# Quad_FC_V10_7-final.net
KiCad netlist of a schematic drawn in Altium Designer
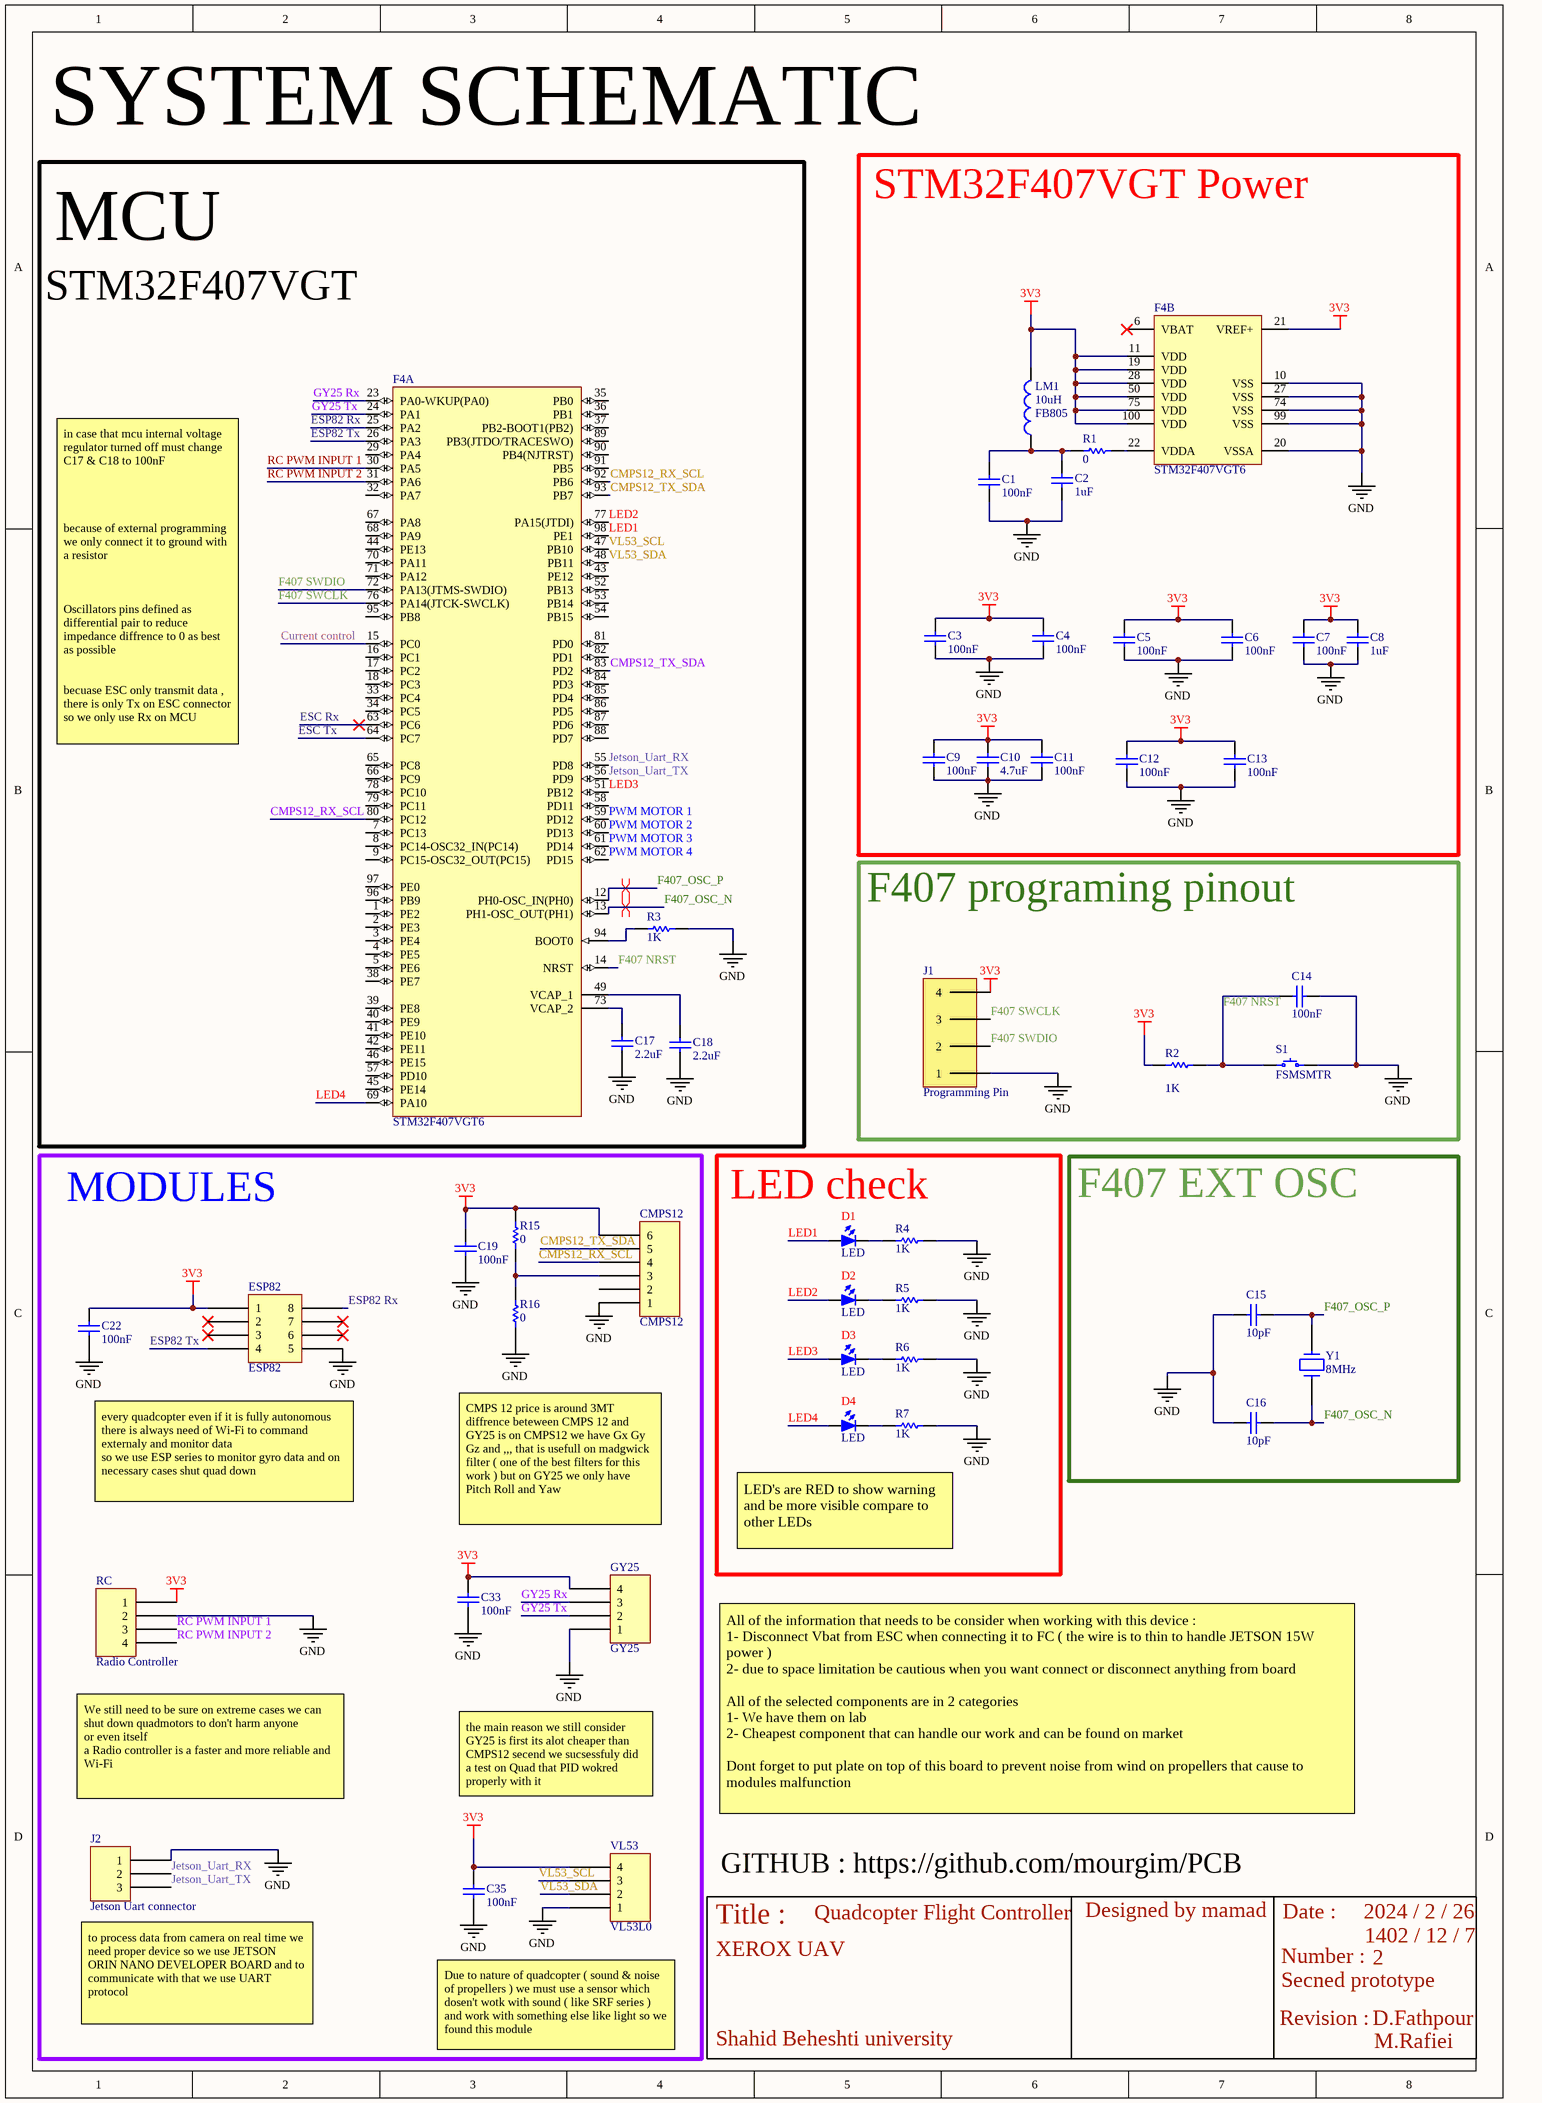
[diagram p0: Quad FC V10.7-final.SchDoc]

(export (version "E")
  (design (tool "Eeschema 10.0.6"))
  (components
    (comp (ref "C1")
      (value "100nF")
      (footprint "CAP0603")
      (description "F407VET6 Power CAP")
      (fields (field (name "DESIGNER") "Abbas Basereh"))
      (libsource (lib "2017AbbasBasereh9365731239 -ver1") (part "CAP SMD PACKAGE"))
    )
    (comp (ref "C2")
      (value "1uF")
      (footprint "CAP0603")
      (description "F407VET6 Power CAP")
      (fields (field (name "DESIGNER") "Abbas Basereh"))
      (libsource (lib "2017AbbasBasereh9365731239 -ver1") (part "CAP SMD PACKAGE"))
    )
    (comp (ref "C3")
      (value "100nF")
      (footprint "CAP0603")
      (description "F407VET6 Power CAP")
      (fields (field (name "DESIGNER") "Abbas Basereh"))
      (libsource (lib "2017AbbasBasereh9365731239 -ver1") (part "CAP SMD PACKAGE"))
    )
    (comp (ref "C4")
      (value "100nF")
      (footprint "CAP0603")
      (description "F407VET6 Power CAP")
      (fields (field (name "DESIGNER") "Abbas Basereh"))
      (libsource (lib "2017AbbasBasereh9365731239 -ver1") (part "CAP SMD PACKAGE"))
    )
    (comp (ref "C5")
      (value "100nF")
      (footprint "CAP0603")
      (description "F407VET6 Power CAP")
      (fields (field (name "DESIGNER") "Abbas Basereh"))
      (libsource (lib "2017AbbasBasereh9365731239 -ver1") (part "CAP SMD PACKAGE"))
    )
    (comp (ref "C6")
      (value "100nF")
      (footprint "CAP0603")
      (description "F407VET6 Power CAP")
      (fields (field (name "DESIGNER") "Abbas Basereh"))
      (libsource (lib "2017AbbasBasereh9365731239 -ver1") (part "CAP SMD PACKAGE"))
    )
    (comp (ref "C7")
      (value "100nF")
      (footprint "CAP0603")
      (description "F407VET6 Power CAP")
      (fields (field (name "DESIGNER") "Abbas Basereh"))
      (libsource (lib "2017AbbasBasereh9365731239 -ver1") (part "CAP SMD PACKAGE"))
    )
    (comp (ref "C8")
      (value "1uF")
      (footprint "CAP0603")
      (description "F407VET6 Power CAP")
      (fields (field (name "DESIGNER") "Abbas Basereh"))
      (libsource (lib "2017AbbasBasereh9365731239 -ver1") (part "CAP SMD PACKAGE"))
    )
    (comp (ref "C9")
      (value "100nF")
      (footprint "CAP0603")
      (description "F407VET6 Power CAP")
      (fields (field (name "DESIGNER") "Abbas Basereh"))
      (libsource (lib "2017AbbasBasereh9365731239 -ver1") (part "CAP SMD PACKAGE"))
    )
    (comp (ref "C10")
      (value "4.7uF")
      (footprint "CAP0603")
      (description "F407VET6 Power CAP")
      (fields (field (name "DESIGNER") "Abbas Basereh"))
      (libsource (lib "2017AbbasBasereh9365731239 -ver1") (part "CAP SMD PACKAGE"))
    )
    (comp (ref "C11")
      (value "100nF")
      (footprint "CAP0603")
      (description "F407VET6 Power CAP")
      (fields (field (name "DESIGNER") "Abbas Basereh"))
      (libsource (lib "2017AbbasBasereh9365731239 -ver1") (part "CAP SMD PACKAGE"))
    )
    (comp (ref "C12")
      (value "100nF")
      (footprint "CAP0603")
      (description "F407VET6 Power CAP")
      (fields (field (name "DESIGNER") "Abbas Basereh"))
      (libsource (lib "2017AbbasBasereh9365731239 -ver1") (part "CAP SMD PACKAGE"))
    )
    (comp (ref "C13")
      (value "100nF")
      (footprint "CAP0603")
      (description "F407VET6 Power CAP")
      (fields (field (name "DESIGNER") "Abbas Basereh"))
      (libsource (lib "2017AbbasBasereh9365731239 -ver1") (part "CAP SMD PACKAGE"))
    )
    (comp (ref "C14")
      (value "100nF")
      (footprint "CAP0603")
      (description "F407VET6 Power CAP")
      (fields (field (name "DESIGNER") "Abbas Basereh"))
      (libsource (lib "2017AbbasBasereh9365731239 -ver1") (part "CAP SMD PACKAGE"))
    )
    (comp (ref "C15")
      (value "10pF")
      (footprint "CAP0603")
      (description "F407VET6 Power CAP")
      (fields (field (name "DESIGNER") "Abbas Basereh"))
      (libsource (lib "2017AbbasBasereh9365731239 -ver1") (part "CAP SMD PACKAGE"))
    )
    (comp (ref "C16")
      (value "10pF")
      (footprint "CAP0603")
      (description "F407VET6 Power CAP")
      (fields (field (name "DESIGNER") "Abbas Basereh"))
      (libsource (lib "2017AbbasBasereh9365731239 -ver1") (part "CAP SMD PACKAGE"))
    )
    (comp (ref "C17")
      (value "2.2uF")
      (footprint "CAP0603")
      (description "F407VET6 Power CAP")
      (fields (field (name "DESIGNER") "Abbas Basereh"))
      (libsource (lib "2017AbbasBasereh9365731239 -ver1") (part "CAP SMD PACKAGE"))
    )
    (comp (ref "C18")
      (value "2.2uF")
      (footprint "CAP0603")
      (description "F407VET6 Power CAP")
      (fields (field (name "DESIGNER") "Abbas Basereh"))
      (libsource (lib "2017AbbasBasereh9365731239 -ver1") (part "CAP SMD PACKAGE"))
    )
    (comp (ref "C19")
      (value "100nF")
      (footprint "CAP0603")
      (description "F407VET6 Power CAP")
      (fields (field (name "DESIGNER") "Abbas Basereh"))
      (libsource (lib "2017AbbasBasereh9365731239 -ver1") (part "CAP SMD PACKAGE"))
    )
    (comp (ref "C22")
      (value "100nF")
      (footprint "CAP0603")
      (description "F407VET6 Power CAP")
      (fields (field (name "DESIGNER") "Abbas Basereh"))
      (libsource (lib "2017AbbasBasereh9365731239 -ver1") (part "CAP SMD PACKAGE"))
    )
    (comp (ref "C33")
      (value "100nF")
      (footprint "CAP0603")
      (description "F407VET6 Power CAP")
      (fields (field (name "DESIGNER") "Abbas Basereh"))
      (libsource (lib "2017AbbasBasereh9365731239 -ver1") (part "CAP SMD PACKAGE"))
    )
    (comp (ref "C35")
      (value "100nF")
      (footprint "CAP0603")
      (description "F407VET6 Power CAP")
      (fields (field (name "DESIGNER") "Abbas Basereh"))
      (libsource (lib "2017AbbasBasereh9365731239 -ver1") (part "CAP SMD PACKAGE"))
    )
    (comp (ref "CMPS12")
      (value "CMPS12")
      (footprint "SAMTEC SSW-106-03-T-S")
      (description "CONN RCPT 6POS 0.1 TIN PCB")
      (fields (field (name "PART NUMBER") "SSW-106-03-T-S") (field (name "MANUFACTURER") "Samtec Inc."))
      (libsource (lib "Celestial Altium Library - altium_library (1)") (part "6 Pin"))
    )
    (comp (ref "D1")
      (value "LED")
      (footprint "0603 - LED")
      (description "Led")
      (fields (field (name "PUBLISHER") "Altium Limited"))
      (libsource (lib "Sajad_Altium_Library") (part "LED"))
    )
    (comp (ref "D2")
      (value "LED")
      (footprint "0603 - LED")
      (description "Led")
      (fields (field (name "PUBLISHER") "Altium Limited"))
      (libsource (lib "Sajad_Altium_Library") (part "LED"))
    )
    (comp (ref "D3")
      (value "LED")
      (footprint "0603 - LED")
      (description "Led")
      (fields (field (name "PUBLISHER") "Altium Limited"))
      (libsource (lib "Sajad_Altium_Library") (part "LED"))
    )
    (comp (ref "D4")
      (value "LED")
      (footprint "0603 - LED")
      (description "Led")
      (fields (field (name "PUBLISHER") "Altium Limited"))
      (libsource (lib "Sajad_Altium_Library") (part "LED"))
    )
    (comp (ref "ESP82")
      (value "ESP82")
      (footprint "HARWIN M20-7830445")
      (description "CONN RCPT 8POS 0.1 GOLD PCB")
      (fields (field (name "PART NUMBER") "M20-7830442") (field (name "MANUFACTURER") "Harwin Inc."))
      (libsource (lib "Celestial Altium Library - altium_library (1)") (part "2X4 PIN DU"))
    )
    (comp (ref "F4")
      (value "STM32F407VGT6")
      (footprint "STM-LQFP100_N")
      (fields (field (name "MANUFACTURER") "STMicroelectronics"))
      (libsource (lib "STMicroelectronics STM32 F4") (part "STM32F407VGT6"))
    )
    (comp (ref "GY25")
      (value "GY25")
      (footprint "SAMTEC SSW-104-03-T-S")
      (description "CONN RCPT 4POS 0.1 TIN PCB")
      (fields (field (name "PART NUMBER") "SSW-104-03-T-S") (field (name "MANUFACTURER") "Samtec Inc."))
      (libsource (lib "Celestial Altium Library - altium_library (1)") (part "4 Pin"))
    )
    (comp (ref "J1")
      (value "Programming Pin")
      (footprint "HEADER 4X1")
      (libsource (lib "AltiumLib1") (part "Header4X1"))
    )
    (comp (ref "J2")
      (value "Jetson Uart connector")
      (footprint "JST XH B3B-XH-A")
      (description "CONN HEADER VERT 3POS 2.5MM")
      (fields
        (field (name "PART NUMBER") "B3B-XH-A(LF)(SN)")
        (field (name "MANUFACTURER") "JST Sales America Inc.")
      )
      (libsource (lib "Celestial Altium Library - altium_library (1)") (part "3 Pin"))
    )
    (comp (ref "LM1")
      (value "10uH")
      (footprint "0805L")
      (description "Inductor")
      (fields (field (name "ALTIUM_VALUE") "FB805") (field (name "PUBLISHER") "Altium Limited"))
      (libsource (lib "2017AbbasBasereh9365731239 -ver1") (part "L SMA 0.25W"))
    )
    (comp (ref "R1")
      (value "0")
      (footprint "RES0603")
      (description "TOTAL SMD RESISTOR PACK")
      (fields (field (name "DESIGNER") "Abbas Basereh"))
      (libsource (lib "2017AbbasBasereh9365731239 -ver1") (part "RES SMD PACKAGE"))
    )
    (comp (ref "R2")
      (value "1K")
      (footprint "RES0603")
      (description "TOTAL SMD RESISTOR PACK")
      (fields (field (name "DESIGNER") "Abbas Basereh"))
      (libsource (lib "2017AbbasBasereh9365731239 -ver1") (part "RES SMD PACKAGE"))
    )
    (comp (ref "R3")
      (value "1K")
      (footprint "RES0603")
      (description "TOTAL SMD RESISTOR PACK")
      (fields (field (name "DESIGNER") "Abbas Basereh"))
      (libsource (lib "2017AbbasBasereh9365731239 -ver1") (part "RES SMD PACKAGE"))
    )
    (comp (ref "R4")
      (value "1K")
      (footprint "RES0603")
      (description "TOTAL SMD RESISTOR PACK")
      (fields (field (name "DESIGNER") "Abbas Basereh"))
      (libsource (lib "2017AbbasBasereh9365731239 -ver1") (part "RES SMD PACKAGE"))
    )
    (comp (ref "R5")
      (value "1K")
      (footprint "RES0603")
      (description "TOTAL SMD RESISTOR PACK")
      (fields (field (name "DESIGNER") "Abbas Basereh"))
      (libsource (lib "2017AbbasBasereh9365731239 -ver1") (part "RES SMD PACKAGE"))
    )
    (comp (ref "R6")
      (value "1K")
      (footprint "RES0603")
      (description "TOTAL SMD RESISTOR PACK")
      (fields (field (name "DESIGNER") "Abbas Basereh"))
      (libsource (lib "2017AbbasBasereh9365731239 -ver1") (part "RES SMD PACKAGE"))
    )
    (comp (ref "R7")
      (value "1K")
      (footprint "RES0603")
      (description "TOTAL SMD RESISTOR PACK")
      (fields (field (name "DESIGNER") "Abbas Basereh"))
      (libsource (lib "2017AbbasBasereh9365731239 -ver1") (part "RES SMD PACKAGE"))
    )
    (comp (ref "R15")
      (value "0")
      (footprint "RES0603")
      (description "TOTAL SMD RESISTOR PACK")
      (fields (field (name "DESIGNER") "Abbas Basereh"))
      (libsource (lib "2017AbbasBasereh9365731239 -ver1") (part "RES SMD PACKAGE"))
    )
    (comp (ref "R16")
      (value "0")
      (footprint "RES0603")
      (description "TOTAL SMD RESISTOR PACK")
      (fields (field (name "DESIGNER") "Abbas Basereh"))
      (libsource (lib "2017AbbasBasereh9365731239 -ver1") (part "RES SMD PACKAGE"))
    )
    (comp (ref "RC")
      (value "Radio Controller")
      (footprint "JST SM04B-GHS-TB")
      (description "CONN HEADER SMD R/A 4POS 1.25MM")
      (fields
        (field (name "PART NUMBER") "SM04B-GHS-TB(LF)(SN)-")
        (field (name "MANUFACTURER") "JST Sales America Inc.")
      )
      (libsource (lib "") (part "4 Pin_1"))
    )
    (comp (ref "S1")
      (value "FSMSMTR")
      (footprint "TE FSMSMTR")
      (description "SWITCH TACTILE SPST-NO 0.05A 24V")
      (fields (field (name "MANUFACTURER") "TE Connectivity ALCOSWITCH Switches"))
      (libsource (lib "Celestial Altium Library - altium_library (1)") (part "SPST-NO 2 PIN"))
    )
    (comp (ref "VL53")
      (value "VL53L0")
      (footprint "JST SM04B-GHS-TB")
      (description "CONN HEADER SMD R/A 4POS 1.25MM")
      (fields
        (field (name "PART NUMBER") "SM04B-GHS-TB(LF)(SN)-")
        (field (name "MANUFACTURER") "JST Sales America Inc.")
      )
      (libsource (lib "Celestial Altium Library - altium_library (1)") (part "4 Pin"))
    )
    (comp (ref "Y1")
      (value "8MHz")
      (footprint "My_Crystal - SMD")
      (description "Crystal")
      (libsource (lib "AMINLIB") (part "CRYSTAL_SMD"))
    )
  )
  (nets
    (net (code "1") (name "/CMPS12_RX_SCL") (class "Default")
      (node (ref "CMPS12") (pin "4") (pinfunction "4_4") (pintype "passive"))
      (node (ref "F4") (pin "80") (pinfunction "PC12_80") (pintype "bidirectional"))
      (node (ref "F4") (pin "92") (pinfunction "PB6_92") (pintype "bidirectional"))
    )
    (net (code "2") (name "/CMPS12_TX_SDA") (class "Default")
      (node (ref "CMPS12") (pin "5") (pinfunction "5_5") (pintype "passive"))
      (node (ref "F4") (pin "83") (pinfunction "PD2_83") (pintype "bidirectional"))
      (node (ref "F4") (pin "93") (pinfunction "PB7_93") (pintype "bidirectional"))
    )
    (net (code "3") (name "/Current control") (class "Default")
      (node (ref "F4") (pin "15") (pinfunction "PC0_15") (pintype "bidirectional"))
    )
    (net (code "4") (name "/ESC Rx") (class "Default")
      (node (ref "F4") (pin "63") (pinfunction "PC6_63") (pintype "bidirectional"))
    )
    (net (code "5") (name "/ESC Tx") (class "Default")
      (node (ref "F4") (pin "64") (pinfunction "PC7_64") (pintype "bidirectional"))
    )
    (net (code "6") (name "/ESP82 Rx") (class "Default")
      (node (ref "ESP82") (pin "8") (pinfunction "8_8") (pintype "passive"))
      (node (ref "F4") (pin "25") (pinfunction "PA2_25") (pintype "bidirectional"))
    )
    (net (code "7") (name "/ESP82 Tx") (class "Default")
      (node (ref "ESP82") (pin "4") (pinfunction "4_4") (pintype "passive"))
      (node (ref "F4") (pin "26") (pinfunction "PA3_26") (pintype "bidirectional"))
    )
    (net (code "8") (name "/F407 NRST") (class "Default")
      (node (ref "C14") (pin "1") (pinfunction "1_1") (pintype "passive"))
      (node (ref "F4") (pin "14") (pinfunction "NRST_14") (pintype "bidirectional"))
      (node (ref "R2") (pin "2") (pinfunction "2_2") (pintype "passive"))
      (node (ref "S1") (pin "1") (pinfunction "1_1") (pintype "passive"))
    )
    (net (code "9") (name "/F407 SWCLK") (class "Default")
      (node (ref "F4") (pin "76") (pinfunction "PA14(JTCK-SWCLK)_76") (pintype "bidirectional"))
      (node (ref "J1") (pin "3") (pinfunction "3_3") (pintype "passive"))
    )
    (net (code "10") (name "/F407 SWDIO") (class "Default")
      (node (ref "F4") (pin "72") (pinfunction "PA13(JTMS-SWDIO)_72") (pintype "bidirectional"))
      (node (ref "J1") (pin "2") (pinfunction "2_2") (pintype "passive"))
    )
    (net (code "11") (name "/F407_OSC_N") (class "Default")
      (node (ref "C16") (pin "1") (pinfunction "1_1") (pintype "passive"))
      (node (ref "F4") (pin "13") (pinfunction "PH1-OSC_OUT(PH1)_13") (pintype "bidirectional"))
      (node (ref "Y1") (pin "1") (pinfunction "1_1") (pintype "passive"))
    )
    (net (code "12") (name "/F407_OSC_P") (class "Default")
      (node (ref "C15") (pin "2") (pinfunction "2_2") (pintype "passive"))
      (node (ref "F4") (pin "12") (pinfunction "PH0-OSC_IN(PH0)_12") (pintype "bidirectional"))
      (node (ref "Y1") (pin "2") (pinfunction "2_2") (pintype "passive"))
    )
    (net (code "13") (name "/GY25 Rx") (class "Default")
      (node (ref "F4") (pin "23") (pinfunction "PA0-WKUP(PA0)_23") (pintype "bidirectional"))
      (node (ref "GY25") (pin "3") (pinfunction "3_3") (pintype "passive"))
    )
    (net (code "14") (name "/GY25 Tx") (class "Default")
      (node (ref "F4") (pin "24") (pinfunction "PA1_24") (pintype "bidirectional"))
      (node (ref "GY25") (pin "2") (pinfunction "2_2") (pintype "passive"))
    )
    (net (code "15") (name "/Jetson_Uart_RX") (class "Default")
      (node (ref "F4") (pin "55") (pinfunction "PD8_55") (pintype "bidirectional"))
      (node (ref "J2") (pin "2") (pinfunction "2_2") (pintype "passive"))
    )
    (net (code "16") (name "/Jetson_Uart_TX") (class "Default")
      (node (ref "F4") (pin "56") (pinfunction "PD9_56") (pintype "bidirectional"))
      (node (ref "J2") (pin "3") (pinfunction "3_3") (pintype "passive"))
    )
    (net (code "17") (name "/LED1") (class "Default")
      (node (ref "D1") (pin "1") (pinfunction "A_1") (pintype "passive"))
      (node (ref "F4") (pin "98") (pinfunction "PE1_98") (pintype "bidirectional"))
    )
    (net (code "18") (name "/LED2") (class "Default")
      (node (ref "D2") (pin "1") (pinfunction "A_1") (pintype "passive"))
      (node (ref "F4") (pin "77") (pinfunction "PA15(JTDI)_77") (pintype "bidirectional"))
    )
    (net (code "19") (name "/LED3") (class "Default")
      (node (ref "D3") (pin "1") (pinfunction "A_1") (pintype "passive"))
      (node (ref "F4") (pin "51") (pinfunction "PB12_51") (pintype "bidirectional"))
    )
    (net (code "20") (name "/LED4") (class "Default")
      (node (ref "D4") (pin "1") (pinfunction "A_1") (pintype "passive"))
      (node (ref "F4") (pin "69") (pinfunction "PA10_69") (pintype "bidirectional"))
    )
    (net (code "21") (name "/PWM MOTOR 1") (class "Default")
      (node (ref "F4") (pin "59") (pinfunction "PD12_59") (pintype "bidirectional"))
    )
    (net (code "22") (name "/PWM MOTOR 2") (class "Default")
      (node (ref "F4") (pin "60") (pinfunction "PD13_60") (pintype "bidirectional"))
    )
    (net (code "23") (name "/PWM MOTOR 3") (class "Default")
      (node (ref "F4") (pin "61") (pinfunction "PD14_61") (pintype "bidirectional"))
    )
    (net (code "24") (name "/PWM MOTOR 4") (class "Default")
      (node (ref "F4") (pin "62") (pinfunction "PD15_62") (pintype "bidirectional"))
    )
    (net (code "25") (name "/RC PWM INPUT 1") (class "Default")
      (node (ref "F4") (pin "30") (pinfunction "PA5_30") (pintype "bidirectional"))
      (node (ref "RC") (pin "3") (pinfunction "3_3") (pintype "passive"))
    )
    (net (code "26") (name "/RC PWM INPUT 2") (class "Default")
      (node (ref "F4") (pin "31") (pinfunction "PA6_31") (pintype "bidirectional"))
      (node (ref "RC") (pin "4") (pinfunction "4_4") (pintype "passive"))
    )
    (net (code "27") (name "/VL53_SCL") (class "Default")
      (node (ref "F4") (pin "47") (pinfunction "PB10_47") (pintype "bidirectional"))
      (node (ref "VL53") (pin "3") (pinfunction "3_3") (pintype "passive"))
    )
    (net (code "28") (name "/VL53_SDA") (class "Default")
      (node (ref "F4") (pin "48") (pinfunction "PB11_48") (pintype "bidirectional"))
      (node (ref "VL53") (pin "2") (pinfunction "2_2") (pintype "passive"))
    )
    (net (code "29") (name "3V3") (class "Default")
      (node (ref "C10") (pin "2") (pinfunction "2_2") (pintype "passive"))
      (node (ref "C11") (pin "2") (pinfunction "2_2") (pintype "passive"))
      (node (ref "C12") (pin "2") (pinfunction "2_2") (pintype "passive"))
      (node (ref "C13") (pin "2") (pinfunction "2_2") (pintype "passive"))
      (node (ref "C19") (pin "1") (pinfunction "1_1") (pintype "passive"))
      (node (ref "C22") (pin "1") (pinfunction "1_1") (pintype "passive"))
      (node (ref "C3") (pin "2") (pinfunction "2_2") (pintype "passive"))
      (node (ref "C33") (pin "1") (pinfunction "1_1") (pintype "passive"))
      (node (ref "C35") (pin "1") (pinfunction "1_1") (pintype "passive"))
      (node (ref "C4") (pin "2") (pinfunction "2_2") (pintype "passive"))
      (node (ref "C5") (pin "2") (pinfunction "2_2") (pintype "passive"))
      (node (ref "C6") (pin "2") (pinfunction "2_2") (pintype "passive"))
      (node (ref "C7") (pin "1") (pinfunction "1_1") (pintype "passive"))
      (node (ref "C8") (pin "1") (pinfunction "1_1") (pintype "passive"))
      (node (ref "C9") (pin "2") (pinfunction "2_2") (pintype "passive"))
      (node (ref "CMPS12") (pin "6") (pinfunction "6_6") (pintype "passive"))
      (node (ref "ESP82") (pin "1") (pinfunction "1_1") (pintype "passive"))
      (node (ref "F4") (pin "100") (pinfunction "VDD_100") (pintype "power_in"))
      (node (ref "F4") (pin "11") (pinfunction "VDD_11") (pintype "power_in"))
      (node (ref "F4") (pin "19") (pinfunction "VDD_19") (pintype "power_in"))
      (node (ref "F4") (pin "21") (pinfunction "VREF+_21") (pintype "power_in"))
      (node (ref "F4") (pin "28") (pinfunction "VDD_28") (pintype "power_in"))
      (node (ref "F4") (pin "50") (pinfunction "VDD_50") (pintype "power_in"))
      (node (ref "F4") (pin "75") (pinfunction "VDD_75") (pintype "power_in"))
      (node (ref "GY25") (pin "4") (pinfunction "4_4") (pintype "passive"))
      (node (ref "J1") (pin "4") (pinfunction "4_4") (pintype "passive"))
      (node (ref "LM1") (pin "2") (pinfunction "2_2") (pintype "passive"))
      (node (ref "R15") (pin "2") (pinfunction "2_2") (pintype "passive"))
      (node (ref "R2") (pin "1") (pinfunction "1_1") (pintype "passive"))
      (node (ref "RC") (pin "1") (pinfunction "1_1") (pintype "passive"))
      (node (ref "VL53") (pin "4") (pinfunction "4_4") (pintype "passive"))
    )
    (net (code "30") (name "GND") (class "Default")
      (node (ref "C1") (pin "1") (pinfunction "1_1") (pintype "passive"))
      (node (ref "C10") (pin "1") (pinfunction "1_1") (pintype "passive"))
      (node (ref "C11") (pin "1") (pinfunction "1_1") (pintype "passive"))
      (node (ref "C12") (pin "1") (pinfunction "1_1") (pintype "passive"))
      (node (ref "C13") (pin "1") (pinfunction "1_1") (pintype "passive"))
      (node (ref "C14") (pin "2") (pinfunction "2_2") (pintype "passive"))
      (node (ref "C15") (pin "1") (pinfunction "1_1") (pintype "passive"))
      (node (ref "C16") (pin "2") (pinfunction "2_2") (pintype "passive"))
      (node (ref "C17") (pin "2") (pinfunction "2_2") (pintype "passive"))
      (node (ref "C18") (pin "2") (pinfunction "2_2") (pintype "passive"))
      (node (ref "C19") (pin "2") (pinfunction "2_2") (pintype "passive"))
      (node (ref "C2") (pin "1") (pinfunction "1_1") (pintype "passive"))
      (node (ref "C22") (pin "2") (pinfunction "2_2") (pintype "passive"))
      (node (ref "C3") (pin "1") (pinfunction "1_1") (pintype "passive"))
      (node (ref "C33") (pin "2") (pinfunction "2_2") (pintype "passive"))
      (node (ref "C35") (pin "2") (pinfunction "2_2") (pintype "passive"))
      (node (ref "C4") (pin "1") (pinfunction "1_1") (pintype "passive"))
      (node (ref "C5") (pin "1") (pinfunction "1_1") (pintype "passive"))
      (node (ref "C6") (pin "1") (pinfunction "1_1") (pintype "passive"))
      (node (ref "C7") (pin "2") (pinfunction "2_2") (pintype "passive"))
      (node (ref "C8") (pin "2") (pinfunction "2_2") (pintype "passive"))
      (node (ref "C9") (pin "1") (pinfunction "1_1") (pintype "passive"))
      (node (ref "CMPS12") (pin "1") (pinfunction "1_1") (pintype "passive"))
      (node (ref "ESP82") (pin "5") (pinfunction "5_5") (pintype "passive"))
      (node (ref "F4") (pin "10") (pinfunction "VSS_10") (pintype "power_in"))
      (node (ref "F4") (pin "20") (pinfunction "VSSA_20") (pintype "power_in"))
      (node (ref "F4") (pin "27") (pinfunction "VSS_27") (pintype "power_in"))
      (node (ref "F4") (pin "74") (pinfunction "VSS_74") (pintype "power_in"))
      (node (ref "F4") (pin "99") (pinfunction "VSS_99") (pintype "power_in"))
      (node (ref "GY25") (pin "1") (pinfunction "1_1") (pintype "passive"))
      (node (ref "J1") (pin "1") (pinfunction "1_1") (pintype "passive"))
      (node (ref "J2") (pin "1") (pinfunction "1_1") (pintype "passive"))
      (node (ref "R16") (pin "1") (pinfunction "1_1") (pintype "passive"))
      (node (ref "R3") (pin "2") (pinfunction "2_2") (pintype "passive"))
      (node (ref "R4") (pin "2") (pinfunction "2_2") (pintype "passive"))
      (node (ref "R5") (pin "2") (pinfunction "2_2") (pintype "passive"))
      (node (ref "R6") (pin "2") (pinfunction "2_2") (pintype "passive"))
      (node (ref "R7") (pin "2") (pinfunction "2_2") (pintype "passive"))
      (node (ref "RC") (pin "2") (pinfunction "2_2") (pintype "passive"))
      (node (ref "S1") (pin "2") (pinfunction "2_2") (pintype "passive"))
      (node (ref "VL53") (pin "1") (pinfunction "1_1") (pintype "passive"))
    )
    (net (code "31") (name "Net-(C1-Pad2)") (class "Default")
      (node (ref "C1") (pin "2") (pinfunction "2_2") (pintype "passive"))
      (node (ref "C2") (pin "2") (pinfunction "2_2") (pintype "passive"))
      (node (ref "LM1") (pin "1") (pinfunction "1_1") (pintype "passive"))
      (node (ref "R1") (pin "1") (pinfunction "1_1") (pintype "passive"))
    )
    (net (code "32") (name "Net-(CMPS12-Pad3)") (class "Default")
      (node (ref "CMPS12") (pin "3") (pinfunction "3_3") (pintype "passive"))
      (node (ref "R15") (pin "1") (pinfunction "1_1") (pintype "passive"))
      (node (ref "R16") (pin "2") (pinfunction "2_2") (pintype "passive"))
    )
    (net (code "33") (name "Net-(D1-K)") (class "Default")
      (node (ref "D1") (pin "2") (pinfunction "K_2") (pintype "passive"))
      (node (ref "R4") (pin "1") (pinfunction "1_1") (pintype "passive"))
    )
    (net (code "34") (name "Net-(D2-K)") (class "Default")
      (node (ref "D2") (pin "2") (pinfunction "K_2") (pintype "passive"))
      (node (ref "R5") (pin "1") (pinfunction "1_1") (pintype "passive"))
    )
    (net (code "35") (name "Net-(D3-K)") (class "Default")
      (node (ref "D3") (pin "2") (pinfunction "K_2") (pintype "passive"))
      (node (ref "R6") (pin "1") (pinfunction "1_1") (pintype "passive"))
    )
    (net (code "36") (name "Net-(D4-K)") (class "Default")
      (node (ref "D4") (pin "2") (pinfunction "K_2") (pintype "passive"))
      (node (ref "R7") (pin "1") (pinfunction "1_1") (pintype "passive"))
    )
    (net (code "37") (name "Net-(F4A-BOOT0)") (class "Default")
      (node (ref "F4") (pin "94") (pinfunction "BOOT0_94") (pintype "input"))
      (node (ref "R3") (pin "1") (pinfunction "1_1") (pintype "passive"))
    )
    (net (code "38") (name "Net-(F4A-VCAP_1)") (class "Default")
      (node (ref "C18") (pin "1") (pinfunction "1_1") (pintype "passive"))
      (node (ref "F4") (pin "49") (pinfunction "VCAP_1_49") (pintype "power_in"))
    )
    (net (code "39") (name "Net-(F4A-VCAP_2)") (class "Default")
      (node (ref "C17") (pin "1") (pinfunction "1_1") (pintype "passive"))
      (node (ref "F4") (pin "73") (pinfunction "VCAP_2_73") (pintype "power_in"))
    )
    (net (code "40") (name "Net-(F4B-VDDA)") (class "Default")
      (node (ref "F4") (pin "22") (pinfunction "VDDA_22") (pintype "power_in"))
      (node (ref "R1") (pin "2") (pinfunction "2_2") (pintype "passive"))
    )
    (net (code "41") (name "unconnected-(CMPS12-Pad2)") (class "Default")
      (node (ref "CMPS12") (pin "2") (pinfunction "2_2") (pintype "passive"))
    )
    (net (code "42") (name "unconnected-(ESP82-Pad2)") (class "Default")
      (node (ref "ESP82") (pin "2") (pinfunction "2_2") (pintype "passive+no_connect"))
    )
    (net (code "43") (name "unconnected-(ESP82-Pad3)") (class "Default")
      (node (ref "ESP82") (pin "3") (pinfunction "3_3") (pintype "passive+no_connect"))
    )
    (net (code "44") (name "unconnected-(ESP82-Pad6)") (class "Default")
      (node (ref "ESP82") (pin "6") (pinfunction "6_6") (pintype "passive+no_connect"))
    )
    (net (code "45") (name "unconnected-(ESP82-Pad7)") (class "Default")
      (node (ref "ESP82") (pin "7") (pinfunction "7_7") (pintype "passive+no_connect"))
    )
    (net (code "46") (name "unconnected-(F4A-PA4-Pad29)") (class "Default")
      (node (ref "F4") (pin "29") (pinfunction "PA4_29") (pintype "bidirectional"))
    )
    (net (code "47") (name "unconnected-(F4A-PA7-Pad32)") (class "Default")
      (node (ref "F4") (pin "32") (pinfunction "PA7_32") (pintype "bidirectional"))
    )
    (net (code "48") (name "unconnected-(F4A-PA8-Pad67)") (class "Default")
      (node (ref "F4") (pin "67") (pinfunction "PA8_67") (pintype "bidirectional"))
    )
    (net (code "49") (name "unconnected-(F4A-PA9-Pad68)") (class "Default")
      (node (ref "F4") (pin "68") (pinfunction "PA9_68") (pintype "bidirectional"))
    )
    (net (code "50") (name "unconnected-(F4A-PA11-Pad70)") (class "Default")
      (node (ref "F4") (pin "70") (pinfunction "PA11_70") (pintype "bidirectional"))
    )
    (net (code "51") (name "unconnected-(F4A-PA12-Pad71)") (class "Default")
      (node (ref "F4") (pin "71") (pinfunction "PA12_71") (pintype "bidirectional"))
    )
    (net (code "52") (name "unconnected-(F4A-PB0-Pad35)") (class "Default")
      (node (ref "F4") (pin "35") (pinfunction "PB0_35") (pintype "bidirectional"))
    )
    (net (code "53") (name "unconnected-(F4A-PB1-Pad36)") (class "Default")
      (node (ref "F4") (pin "36") (pinfunction "PB1_36") (pintype "bidirectional"))
    )
    (net (code "54") (name "unconnected-(F4A-PB2-BOOT1(PB2)-Pad37)") (class "Default")
      (node (ref "F4") (pin "37") (pinfunction "PB2-BOOT1(PB2)_37") (pintype "bidirectional"))
    )
    (net (code "55") (name "unconnected-(F4A-PB3(JTDO{slash}TRACESWO)-Pad89)") (class "Default")
      (node (ref "F4") (pin "89") (pinfunction "PB3(JTDO/TRACESWO)_89") (pintype "bidirectional"))
    )
    (net (code "56") (name "unconnected-(F4A-PB4(NJTRST)-Pad90)") (class "Default")
      (node (ref "F4") (pin "90") (pinfunction "PB4(NJTRST)_90") (pintype "bidirectional"))
    )
    (net (code "57") (name "unconnected-(F4A-PB5-Pad91)") (class "Default")
      (node (ref "F4") (pin "91") (pinfunction "PB5_91") (pintype "bidirectional"))
    )
    (net (code "58") (name "unconnected-(F4A-PB8-Pad95)") (class "Default")
      (node (ref "F4") (pin "95") (pinfunction "PB8_95") (pintype "bidirectional"))
    )
    (net (code "59") (name "unconnected-(F4A-PB9-Pad96)") (class "Default")
      (node (ref "F4") (pin "96") (pinfunction "PB9_96") (pintype "bidirectional"))
    )
    (net (code "60") (name "unconnected-(F4A-PB13-Pad52)") (class "Default")
      (node (ref "F4") (pin "52") (pinfunction "PB13_52") (pintype "bidirectional"))
    )
    (net (code "61") (name "unconnected-(F4A-PB14-Pad53)") (class "Default")
      (node (ref "F4") (pin "53") (pinfunction "PB14_53") (pintype "bidirectional"))
    )
    (net (code "62") (name "unconnected-(F4A-PB15-Pad54)") (class "Default")
      (node (ref "F4") (pin "54") (pinfunction "PB15_54") (pintype "bidirectional"))
    )
    (net (code "63") (name "unconnected-(F4A-PC1-Pad16)") (class "Default")
      (node (ref "F4") (pin "16") (pinfunction "PC1_16") (pintype "bidirectional"))
    )
    (net (code "64") (name "unconnected-(F4A-PC2-Pad17)") (class "Default")
      (node (ref "F4") (pin "17") (pinfunction "PC2_17") (pintype "bidirectional"))
    )
    (net (code "65") (name "unconnected-(F4A-PC3-Pad18)") (class "Default")
      (node (ref "F4") (pin "18") (pinfunction "PC3_18") (pintype "bidirectional"))
    )
    (net (code "66") (name "unconnected-(F4A-PC4-Pad33)") (class "Default")
      (node (ref "F4") (pin "33") (pinfunction "PC4_33") (pintype "bidirectional"))
    )
    (net (code "67") (name "unconnected-(F4A-PC5-Pad34)") (class "Default")
      (node (ref "F4") (pin "34") (pinfunction "PC5_34") (pintype "bidirectional"))
    )
    (net (code "68") (name "unconnected-(F4A-PC8-Pad65)") (class "Default")
      (node (ref "F4") (pin "65") (pinfunction "PC8_65") (pintype "bidirectional"))
    )
    (net (code "69") (name "unconnected-(F4A-PC9-Pad66)") (class "Default")
      (node (ref "F4") (pin "66") (pinfunction "PC9_66") (pintype "bidirectional"))
    )
    (net (code "70") (name "unconnected-(F4A-PC10-Pad78)") (class "Default")
      (node (ref "F4") (pin "78") (pinfunction "PC10_78") (pintype "bidirectional"))
    )
    (net (code "71") (name "unconnected-(F4A-PC11-Pad79)") (class "Default")
      (node (ref "F4") (pin "79") (pinfunction "PC11_79") (pintype "bidirectional"))
    )
    (net (code "72") (name "unconnected-(F4A-PC13-Pad7)") (class "Default")
      (node (ref "F4") (pin "7") (pinfunction "PC13_7") (pintype "bidirectional"))
    )
    (net (code "73") (name "unconnected-(F4A-PC14-OSC32_IN(PC14)-Pad8)") (class "Default")
      (node (ref "F4") (pin "8") (pinfunction "PC14-OSC32_IN(PC14)_8") (pintype "bidirectional"))
    )
    (net (code "74") (name "unconnected-(F4A-PC15-OSC32_OUT(PC15)-Pad9)") (class "Default")
      (node (ref "F4") (pin "9") (pinfunction "PC15-OSC32_OUT(PC15)_9") (pintype "bidirectional"))
    )
    (net (code "75") (name "unconnected-(F4A-PD0-Pad81)") (class "Default")
      (node (ref "F4") (pin "81") (pinfunction "PD0_81") (pintype "bidirectional"))
    )
    (net (code "76") (name "unconnected-(F4A-PD1-Pad82)") (class "Default")
      (node (ref "F4") (pin "82") (pinfunction "PD1_82") (pintype "bidirectional"))
    )
    (net (code "77") (name "unconnected-(F4A-PD3-Pad84)") (class "Default")
      (node (ref "F4") (pin "84") (pinfunction "PD3_84") (pintype "bidirectional"))
    )
    (net (code "78") (name "unconnected-(F4A-PD4-Pad85)") (class "Default")
      (node (ref "F4") (pin "85") (pinfunction "PD4_85") (pintype "bidirectional"))
    )
    (net (code "79") (name "unconnected-(F4A-PD5-Pad86)") (class "Default")
      (node (ref "F4") (pin "86") (pinfunction "PD5_86") (pintype "bidirectional"))
    )
    (net (code "80") (name "unconnected-(F4A-PD6-Pad87)") (class "Default")
      (node (ref "F4") (pin "87") (pinfunction "PD6_87") (pintype "bidirectional"))
    )
    (net (code "81") (name "unconnected-(F4A-PD7-Pad88)") (class "Default")
      (node (ref "F4") (pin "88") (pinfunction "PD7_88") (pintype "bidirectional"))
    )
    (net (code "82") (name "unconnected-(F4A-PD10-Pad57)") (class "Default")
      (node (ref "F4") (pin "57") (pinfunction "PD10_57") (pintype "bidirectional"))
    )
    (net (code "83") (name "unconnected-(F4A-PD11-Pad58)") (class "Default")
      (node (ref "F4") (pin "58") (pinfunction "PD11_58") (pintype "bidirectional"))
    )
    (net (code "84") (name "unconnected-(F4A-PE0-Pad97)") (class "Default")
      (node (ref "F4") (pin "97") (pinfunction "PE0_97") (pintype "bidirectional"))
    )
    (net (code "85") (name "unconnected-(F4A-PE2-Pad1)") (class "Default")
      (node (ref "F4") (pin "1") (pinfunction "PE2_1") (pintype "bidirectional"))
    )
    (net (code "86") (name "unconnected-(F4A-PE3-Pad2)") (class "Default")
      (node (ref "F4") (pin "2") (pinfunction "PE3_2") (pintype "bidirectional"))
    )
    (net (code "87") (name "unconnected-(F4A-PE4-Pad3)") (class "Default")
      (node (ref "F4") (pin "3") (pinfunction "PE4_3") (pintype "bidirectional"))
    )
    (net (code "88") (name "unconnected-(F4A-PE5-Pad4)") (class "Default")
      (node (ref "F4") (pin "4") (pinfunction "PE5_4") (pintype "bidirectional"))
    )
    (net (code "89") (name "unconnected-(F4A-PE6-Pad5)") (class "Default")
      (node (ref "F4") (pin "5") (pinfunction "PE6_5") (pintype "bidirectional"))
    )
    (net (code "90") (name "unconnected-(F4A-PE7-Pad38)") (class "Default")
      (node (ref "F4") (pin "38") (pinfunction "PE7_38") (pintype "bidirectional"))
    )
    (net (code "91") (name "unconnected-(F4A-PE8-Pad39)") (class "Default")
      (node (ref "F4") (pin "39") (pinfunction "PE8_39") (pintype "bidirectional"))
    )
    (net (code "92") (name "unconnected-(F4A-PE9-Pad40)") (class "Default")
      (node (ref "F4") (pin "40") (pinfunction "PE9_40") (pintype "bidirectional"))
    )
    (net (code "93") (name "unconnected-(F4A-PE10-Pad41)") (class "Default")
      (node (ref "F4") (pin "41") (pinfunction "PE10_41") (pintype "bidirectional"))
    )
    (net (code "94") (name "unconnected-(F4A-PE11-Pad42)") (class "Default")
      (node (ref "F4") (pin "42") (pinfunction "PE11_42") (pintype "bidirectional"))
    )
    (net (code "95") (name "unconnected-(F4A-PE12-Pad43)") (class "Default")
      (node (ref "F4") (pin "43") (pinfunction "PE12_43") (pintype "bidirectional"))
    )
    (net (code "96") (name "unconnected-(F4A-PE13-Pad44)") (class "Default")
      (node (ref "F4") (pin "44") (pinfunction "PE13_44") (pintype "bidirectional"))
    )
    (net (code "97") (name "unconnected-(F4A-PE14-Pad45)") (class "Default")
      (node (ref "F4") (pin "45") (pinfunction "PE14_45") (pintype "bidirectional"))
    )
    (net (code "98") (name "unconnected-(F4A-PE15-Pad46)") (class "Default")
      (node (ref "F4") (pin "46") (pinfunction "PE15_46") (pintype "bidirectional"))
    )
    (net (code "99") (name "unconnected-(F4B-VBAT-Pad6)") (class "Default")
      (node (ref "F4") (pin "6") (pinfunction "VBAT_6") (pintype "power_in+no_connect"))
    )
  )
)
